# Drinkro.net
KiCad netlist of a schematic drawn in EAGLE
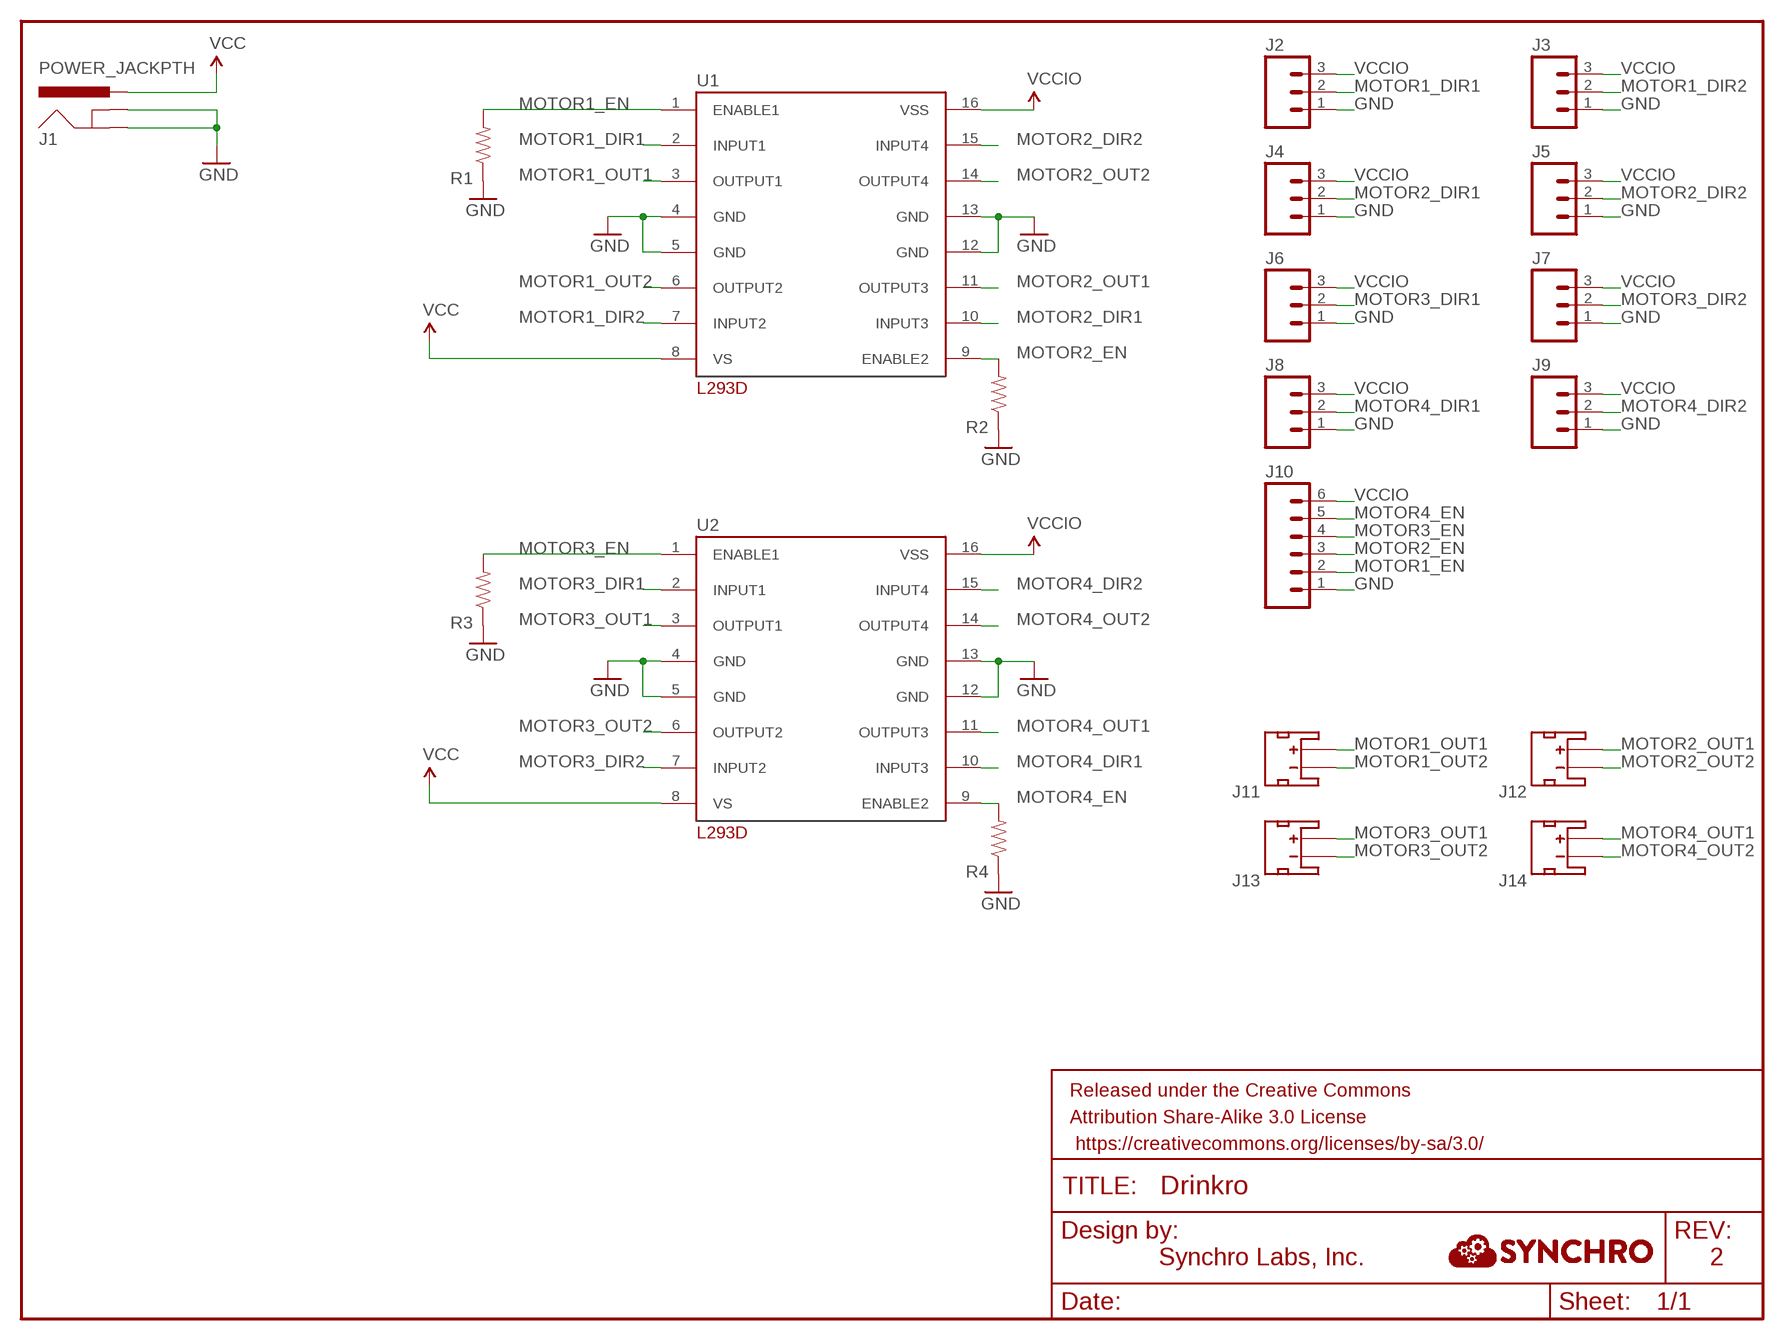
[diagram p0: schematic, sheet 1]

(export (version "E")
  (design (tool "Eeschema 10.0.6"))
  (components
    (comp (ref "FRAME1")
      (value "FRAME-LETTER")
      (footprint "eagle-import:CREATIVE_COMMONS")
      (libsource (lib "eagle-import") (part "FRAME-LETTER"))
    )
    (comp (ref "J1")
      (value "POWER_JACKPTH")
      (footprint "eagle-import:POWER_JACK_PTH")
      (libsource (lib "eagle-import") (part "POWER_JACKPTH"))
    )
    (comp (ref "J2")
      (value "M03PTH")
      (footprint "eagle-import:1X03")
      (libsource (lib "eagle-import") (part "M03PTH"))
    )
    (comp (ref "J3")
      (value "M03PTH")
      (footprint "eagle-import:1X03")
      (libsource (lib "eagle-import") (part "M03PTH"))
    )
    (comp (ref "J4")
      (value "M03PTH")
      (footprint "eagle-import:1X03")
      (libsource (lib "eagle-import") (part "M03PTH"))
    )
    (comp (ref "J5")
      (value "M03PTH")
      (footprint "eagle-import:1X03")
      (libsource (lib "eagle-import") (part "M03PTH"))
    )
    (comp (ref "J6")
      (value "M03PTH")
      (footprint "eagle-import:1X03")
      (libsource (lib "eagle-import") (part "M03PTH"))
    )
    (comp (ref "J7")
      (value "M03PTH")
      (footprint "eagle-import:1X03")
      (libsource (lib "eagle-import") (part "M03PTH"))
    )
    (comp (ref "J8")
      (value "M03PTH")
      (footprint "eagle-import:1X03")
      (libsource (lib "eagle-import") (part "M03PTH"))
    )
    (comp (ref "J9")
      (value "M03PTH")
      (footprint "eagle-import:1X03")
      (libsource (lib "eagle-import") (part "M03PTH"))
    )
    (comp (ref "J10")
      (value "M06SILK_FEMALE_PTH")
      (footprint "eagle-import:1X06")
      (libsource (lib "eagle-import") (part "M06SILK_FEMALE_PTH"))
    )
    (comp (ref "J11")
      (value "JST_2MM_MALE")
      (footprint "eagle-import:JST-2-SMD")
      (libsource (lib "eagle-import") (part "JST_2MM_MALE"))
    )
    (comp (ref "J12")
      (value "JST_2MM_MALE")
      (footprint "eagle-import:JST-2-SMD")
      (libsource (lib "eagle-import") (part "JST_2MM_MALE"))
    )
    (comp (ref "J13")
      (value "JST_2MM_MALE")
      (footprint "eagle-import:JST-2-SMD")
      (libsource (lib "eagle-import") (part "JST_2MM_MALE"))
    )
    (comp (ref "J14")
      (value "JST_2MM_MALE")
      (footprint "eagle-import:JST-2-SMD")
      (libsource (lib "eagle-import") (part "JST_2MM_MALE"))
    )
    (comp (ref "R1")
      (value "RESISTOR0805-RES")
      (footprint "eagle-import:0805")
      (libsource (lib "eagle-import") (part "RESISTOR0805-RES"))
    )
    (comp (ref "R2")
      (value "RESISTOR0805-RES")
      (footprint "eagle-import:0805")
      (libsource (lib "eagle-import") (part "RESISTOR0805-RES"))
    )
    (comp (ref "R3")
      (value "RESISTOR0805-RES")
      (footprint "eagle-import:0805")
      (libsource (lib "eagle-import") (part "RESISTOR0805-RES"))
    )
    (comp (ref "R4")
      (value "RESISTOR0805-RES")
      (footprint "eagle-import:0805")
      (libsource (lib "eagle-import") (part "RESISTOR0805-RES"))
    )
    (comp (ref "U1")
      (value "L293D")
      (footprint "eagle-import:DIP")
      (libsource (lib "eagle-import") (part "L293D"))
    )
    (comp (ref "U2")
      (value "L293D")
      (footprint "eagle-import:DIP")
      (libsource (lib "eagle-import") (part "L293D"))
    )
  )
  (nets
    (net (code "1") (name "/MOTOR1_DIR1") (class "Default")
      (node (ref "J2") (pin "2") (pinfunction "2_2") (pintype "passive"))
      (node (ref "U1") (pin "2") (pinfunction "INPUT1_2") (pintype "input"))
    )
    (net (code "2") (name "/MOTOR1_DIR2") (class "Default")
      (node (ref "J3") (pin "2") (pinfunction "2_2") (pintype "passive"))
      (node (ref "U1") (pin "7") (pinfunction "INPUT2_7") (pintype "input"))
    )
    (net (code "3") (name "/MOTOR1_EN") (class "Default")
      (node (ref "J10") (pin "2") (pinfunction "2_2") (pintype "passive"))
      (node (ref "R1") (pin "2") (pinfunction "2_2") (pintype "passive"))
      (node (ref "U1") (pin "1") (pinfunction "ENABLE1_1") (pintype "input"))
    )
    (net (code "4") (name "/MOTOR1_OUT1") (class "Default")
      (node (ref "J11") (pin "2") (pinfunction "+_2") (pintype "bidirectional"))
      (node (ref "U1") (pin "3") (pinfunction "OUTPUT1_3") (pintype "output"))
    )
    (net (code "5") (name "/MOTOR1_OUT2") (class "Default")
      (node (ref "J11") (pin "1") (pinfunction "-_1") (pintype "bidirectional"))
      (node (ref "U1") (pin "6") (pinfunction "OUTPUT2_6") (pintype "output"))
    )
    (net (code "6") (name "/MOTOR2_DIR1") (class "Default")
      (node (ref "J4") (pin "2") (pinfunction "2_2") (pintype "passive"))
      (node (ref "U1") (pin "10") (pinfunction "INPUT3_10") (pintype "input"))
    )
    (net (code "7") (name "/MOTOR2_DIR2") (class "Default")
      (node (ref "J5") (pin "2") (pinfunction "2_2") (pintype "passive"))
      (node (ref "U1") (pin "15") (pinfunction "INPUT4_15") (pintype "input"))
    )
    (net (code "8") (name "/MOTOR2_EN") (class "Default")
      (node (ref "J10") (pin "3") (pinfunction "3_3") (pintype "passive"))
      (node (ref "R2") (pin "2") (pinfunction "2_2") (pintype "passive"))
      (node (ref "U1") (pin "9") (pinfunction "ENABLE2_9") (pintype "input"))
    )
    (net (code "9") (name "/MOTOR2_OUT1") (class "Default")
      (node (ref "J12") (pin "2") (pinfunction "+_2") (pintype "bidirectional"))
      (node (ref "U1") (pin "11") (pinfunction "OUTPUT3_11") (pintype "output"))
    )
    (net (code "10") (name "/MOTOR2_OUT2") (class "Default")
      (node (ref "J12") (pin "1") (pinfunction "-_1") (pintype "bidirectional"))
      (node (ref "U1") (pin "14") (pinfunction "OUTPUT4_14") (pintype "output"))
    )
    (net (code "11") (name "/MOTOR3_DIR1") (class "Default")
      (node (ref "J6") (pin "2") (pinfunction "2_2") (pintype "passive"))
      (node (ref "U2") (pin "2") (pinfunction "INPUT1_2") (pintype "input"))
    )
    (net (code "12") (name "/MOTOR3_DIR2") (class "Default")
      (node (ref "J7") (pin "2") (pinfunction "2_2") (pintype "passive"))
      (node (ref "U2") (pin "7") (pinfunction "INPUT2_7") (pintype "input"))
    )
    (net (code "13") (name "/MOTOR3_EN") (class "Default")
      (node (ref "J10") (pin "4") (pinfunction "4_4") (pintype "passive"))
      (node (ref "R3") (pin "2") (pinfunction "2_2") (pintype "passive"))
      (node (ref "U2") (pin "1") (pinfunction "ENABLE1_1") (pintype "input"))
    )
    (net (code "14") (name "/MOTOR3_OUT1") (class "Default")
      (node (ref "J13") (pin "2") (pinfunction "+_2") (pintype "bidirectional"))
      (node (ref "U2") (pin "3") (pinfunction "OUTPUT1_3") (pintype "output"))
    )
    (net (code "15") (name "/MOTOR3_OUT2") (class "Default")
      (node (ref "J13") (pin "1") (pinfunction "-_1") (pintype "bidirectional"))
      (node (ref "U2") (pin "6") (pinfunction "OUTPUT2_6") (pintype "output"))
    )
    (net (code "16") (name "/MOTOR4_DIR1") (class "Default")
      (node (ref "J8") (pin "2") (pinfunction "2_2") (pintype "passive"))
      (node (ref "U2") (pin "10") (pinfunction "INPUT3_10") (pintype "input"))
    )
    (net (code "17") (name "/MOTOR4_DIR2") (class "Default")
      (node (ref "J9") (pin "2") (pinfunction "2_2") (pintype "passive"))
      (node (ref "U2") (pin "15") (pinfunction "INPUT4_15") (pintype "input"))
    )
    (net (code "18") (name "/MOTOR4_EN") (class "Default")
      (node (ref "J10") (pin "5") (pinfunction "5_5") (pintype "passive"))
      (node (ref "R4") (pin "2") (pinfunction "2_2") (pintype "passive"))
      (node (ref "U2") (pin "9") (pinfunction "ENABLE2_9") (pintype "input"))
    )
    (net (code "19") (name "/MOTOR4_OUT1") (class "Default")
      (node (ref "J14") (pin "2") (pinfunction "+_2") (pintype "bidirectional"))
      (node (ref "U2") (pin "11") (pinfunction "OUTPUT3_11") (pintype "output"))
    )
    (net (code "20") (name "/MOTOR4_OUT2") (class "Default")
      (node (ref "J14") (pin "1") (pinfunction "-_1") (pintype "bidirectional"))
      (node (ref "U2") (pin "14") (pinfunction "OUTPUT4_14") (pintype "output"))
    )
    (net (code "21") (name "GND") (class "Default")
      (node (ref "J1") (pin "GND") (pinfunction "GND_GND") (pintype "bidirectional"))
      (node (ref "J1") (pin "GNDBREAK") (pinfunction "GNDBREAK_GNDBREAK") (pintype "bidirectional"))
      (node (ref "J10") (pin "1") (pinfunction "1_1") (pintype "passive"))
      (node (ref "J2") (pin "1") (pinfunction "1_1") (pintype "passive"))
      (node (ref "J3") (pin "1") (pinfunction "1_1") (pintype "passive"))
      (node (ref "J4") (pin "1") (pinfunction "1_1") (pintype "passive"))
      (node (ref "J5") (pin "1") (pinfunction "1_1") (pintype "passive"))
      (node (ref "J6") (pin "1") (pinfunction "1_1") (pintype "passive"))
      (node (ref "J7") (pin "1") (pinfunction "1_1") (pintype "passive"))
      (node (ref "J8") (pin "1") (pinfunction "1_1") (pintype "passive"))
      (node (ref "J9") (pin "1") (pinfunction "1_1") (pintype "passive"))
      (node (ref "R1") (pin "1") (pinfunction "1_1") (pintype "passive"))
      (node (ref "R2") (pin "1") (pinfunction "1_1") (pintype "passive"))
      (node (ref "R3") (pin "1") (pinfunction "1_1") (pintype "passive"))
      (node (ref "R4") (pin "1") (pinfunction "1_1") (pintype "passive"))
      (node (ref "U1") (pin "12") (pinfunction "GND_12") (pintype "bidirectional"))
      (node (ref "U1") (pin "13") (pinfunction "GND_13") (pintype "bidirectional"))
      (node (ref "U1") (pin "4") (pinfunction "GND_4") (pintype "bidirectional"))
      (node (ref "U1") (pin "5") (pinfunction "GND_5") (pintype "bidirectional"))
      (node (ref "U2") (pin "12") (pinfunction "GND_12") (pintype "bidirectional"))
      (node (ref "U2") (pin "13") (pinfunction "GND_13") (pintype "bidirectional"))
      (node (ref "U2") (pin "4") (pinfunction "GND_4") (pintype "bidirectional"))
      (node (ref "U2") (pin "5") (pinfunction "GND_5") (pintype "bidirectional"))
    )
    (net (code "22") (name "VCC") (class "Default")
      (node (ref "J1") (pin "PWR") (pinfunction "PWR_PWR") (pintype "bidirectional"))
      (node (ref "U1") (pin "8") (pinfunction "VS_8") (pintype "power_in"))
      (node (ref "U2") (pin "8") (pinfunction "VS_8") (pintype "power_in"))
    )
    (net (code "23") (name "VCCIO") (class "Default")
      (node (ref "J10") (pin "6") (pinfunction "6_6") (pintype "passive"))
      (node (ref "J2") (pin "3") (pinfunction "3_3") (pintype "passive"))
      (node (ref "J3") (pin "3") (pinfunction "3_3") (pintype "passive"))
      (node (ref "J4") (pin "3") (pinfunction "3_3") (pintype "passive"))
      (node (ref "J5") (pin "3") (pinfunction "3_3") (pintype "passive"))
      (node (ref "J6") (pin "3") (pinfunction "3_3") (pintype "passive"))
      (node (ref "J7") (pin "3") (pinfunction "3_3") (pintype "passive"))
      (node (ref "J8") (pin "3") (pinfunction "3_3") (pintype "passive"))
      (node (ref "J9") (pin "3") (pinfunction "3_3") (pintype "passive"))
      (node (ref "U1") (pin "16") (pinfunction "VSS_16") (pintype "power_in"))
      (node (ref "U2") (pin "16") (pinfunction "VSS_16") (pintype "power_in"))
    )
    (net (code "24") (name "unconnected-(J11-PAD1-PadNC1)") (class "Default")
      (node (ref "J11") (pin "NC1") (pinfunction "PAD1_NC1") (pintype "bidirectional"))
    )
    (net (code "25") (name "unconnected-(J11-PAD2-PadNC2)") (class "Default")
      (node (ref "J11") (pin "NC2") (pinfunction "PAD2_NC2") (pintype "bidirectional"))
    )
    (net (code "26") (name "unconnected-(J12-PAD1-PadNC1)") (class "Default")
      (node (ref "J12") (pin "NC1") (pinfunction "PAD1_NC1") (pintype "bidirectional"))
    )
    (net (code "27") (name "unconnected-(J12-PAD2-PadNC2)") (class "Default")
      (node (ref "J12") (pin "NC2") (pinfunction "PAD2_NC2") (pintype "bidirectional"))
    )
    (net (code "28") (name "unconnected-(J13-PAD1-PadNC1)") (class "Default")
      (node (ref "J13") (pin "NC1") (pinfunction "PAD1_NC1") (pintype "bidirectional"))
    )
    (net (code "29") (name "unconnected-(J13-PAD2-PadNC2)") (class "Default")
      (node (ref "J13") (pin "NC2") (pinfunction "PAD2_NC2") (pintype "bidirectional"))
    )
    (net (code "30") (name "unconnected-(J14-PAD1-PadNC1)") (class "Default")
      (node (ref "J14") (pin "NC1") (pinfunction "PAD1_NC1") (pintype "bidirectional"))
    )
    (net (code "31") (name "unconnected-(J14-PAD2-PadNC2)") (class "Default")
      (node (ref "J14") (pin "NC2") (pinfunction "PAD2_NC2") (pintype "bidirectional"))
    )
  )
)
